# ir-sensor-breakout-mk-1_0.net
KiCad netlist of a schematic drawn in EAGLE
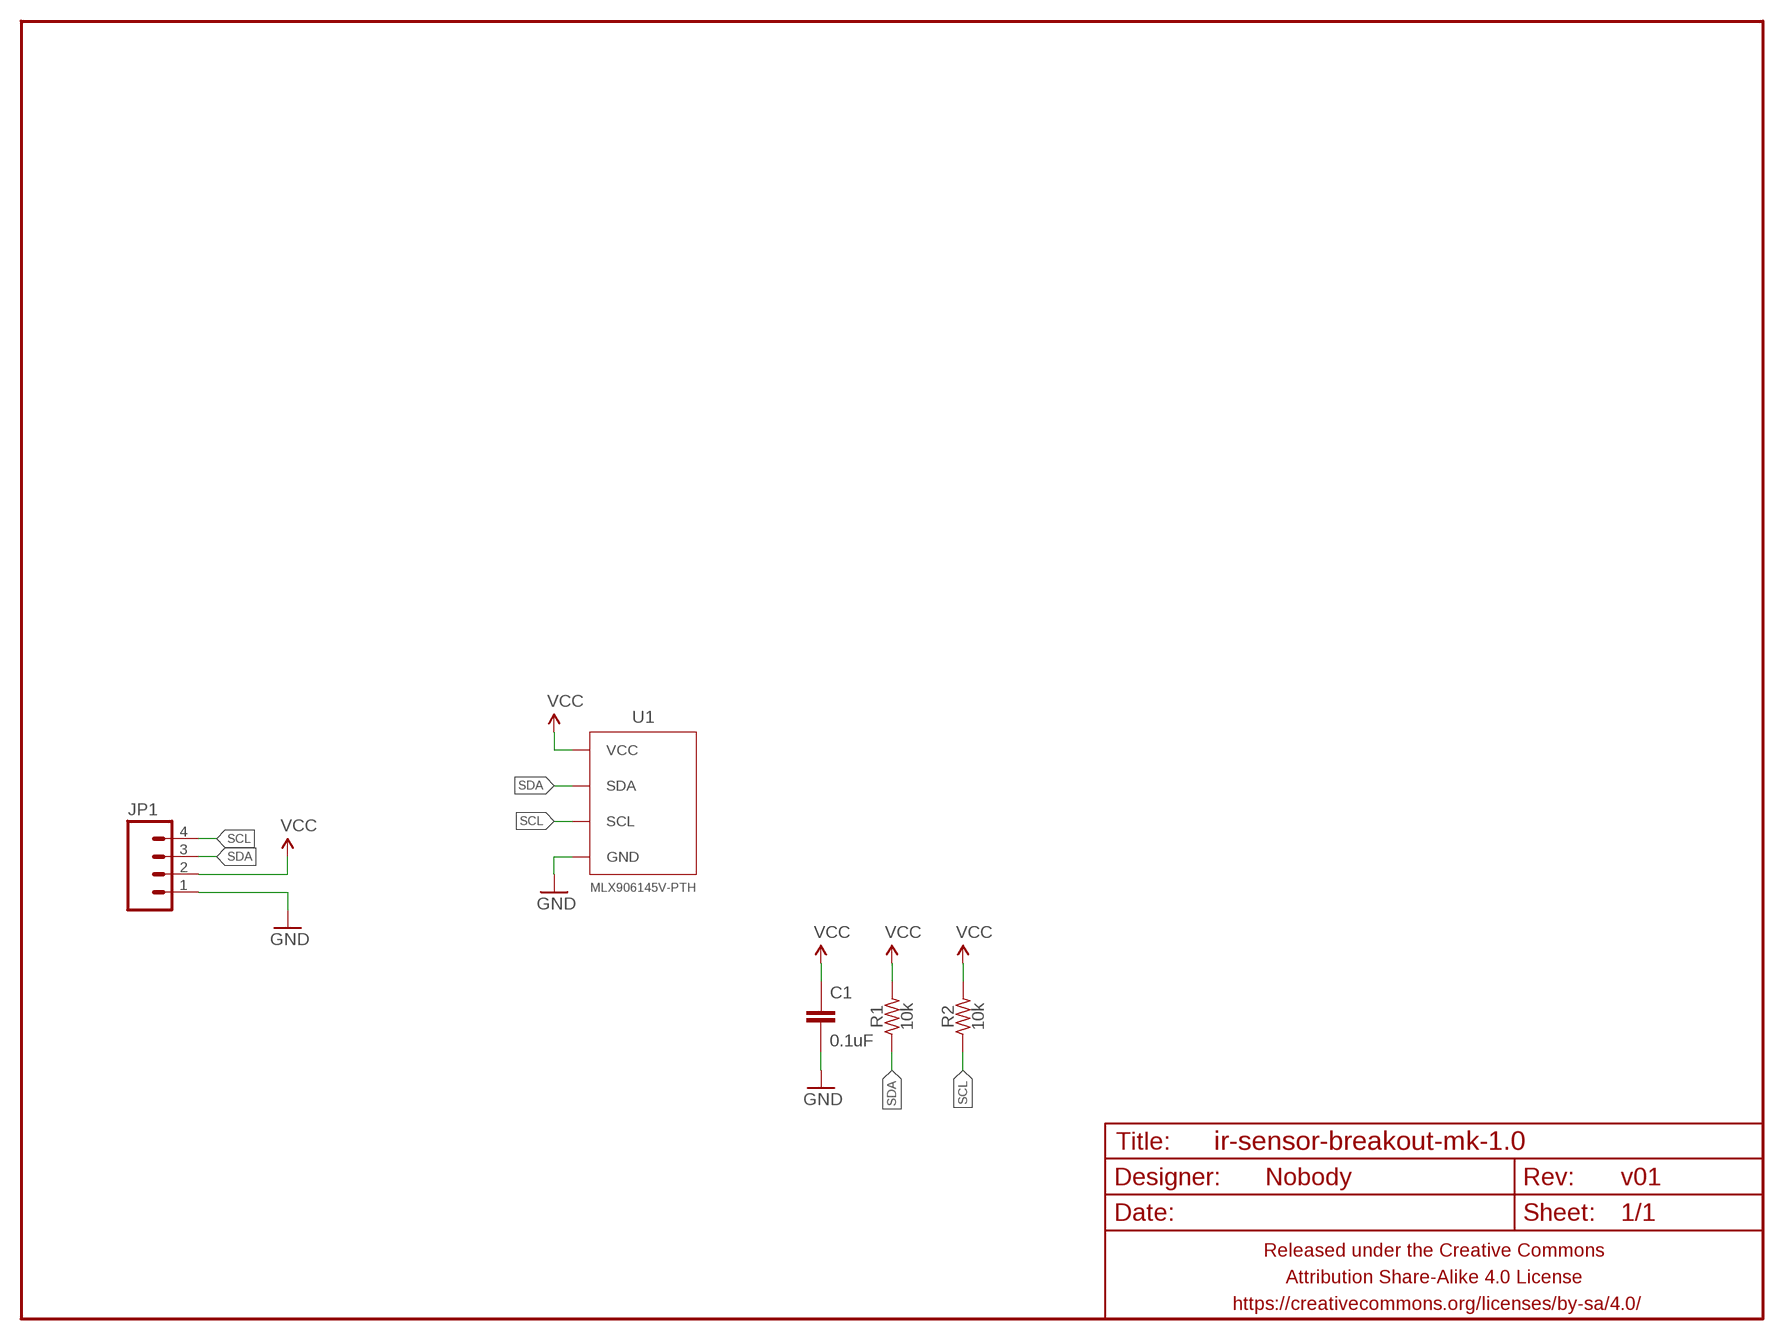
[diagram p0: schematic, sheet 1]

(export (version "E")
  (design (tool "Eeschema 10.0.6"))
  (components
    (comp (ref "C1")
      (value "0.1uF")
      (footprint "eagle-import:C025-024X044")
      (libsource (lib "eagle-import") (part "CAPACITOR-CERAMIC025-024X044"))
    )
    (comp (ref "FRAME1")
      (value "FRAME-LETTERNO_PACKAGE")
      (footprint "eagle-import:DUMMY")
      (fields (field (name "DESIGNER") "Nobody"))
      (libsource (lib "eagle-import") (part "FRAME-LETTERNO_PACKAGE"))
    )
    (comp (ref "JP1")
      (value "M04JST-PTH")
      (footprint "eagle-import:JST-4-PH-RA-PTH")
      (libsource (lib "eagle-import") (part "M04JST-PTH"))
    )
    (comp (ref "R1")
      (value "10k")
      (footprint "eagle-import:RESISTOR-AXIAL-PTH-7.62MM")
      (libsource (lib "eagle-import") (part "RESISTORPTH-AXIAL-7.62MM"))
    )
    (comp (ref "R2")
      (value "10k")
      (footprint "eagle-import:RESISTOR-AXIAL-PTH-7.62MM")
      (libsource (lib "eagle-import") (part "RESISTORPTH-AXIAL-7.62MM"))
    )
    (comp (ref "U1")
      (value "MLX906145V-PTH")
      (footprint "eagle-import:TO-39-4")
      (libsource (lib "eagle-import") (part "MLX906145V-PTH"))
    )
  )
  (nets
    (net (code "1") (name "GND") (class "Default")
      (node (ref "C1") (pin "2") (pinfunction "2_2") (pintype "passive"))
      (node (ref "JP1") (pin "1") (pinfunction "1_1") (pintype "passive"))
      (node (ref "U1") (pin "4") (pinfunction "GND_4") (pintype "bidirectional"))
    )
    (net (code "2") (name "SCL") (class "Default")
      (node (ref "JP1") (pin "4") (pinfunction "4_4") (pintype "passive"))
      (node (ref "R2") (pin "P$1") (pinfunction "1_P$1") (pintype "passive"))
      (node (ref "U1") (pin "1") (pinfunction "SCL_1") (pintype "bidirectional"))
    )
    (net (code "3") (name "SDA") (class "Default")
      (node (ref "JP1") (pin "3") (pinfunction "3_3") (pintype "passive"))
      (node (ref "R1") (pin "P$1") (pinfunction "1_P$1") (pintype "passive"))
      (node (ref "U1") (pin "2") (pinfunction "SDA_2") (pintype "bidirectional"))
    )
    (net (code "4") (name "VCC") (class "Default")
      (node (ref "C1") (pin "1") (pinfunction "1_1") (pintype "passive"))
      (node (ref "JP1") (pin "2") (pinfunction "2_2") (pintype "passive"))
      (node (ref "R1") (pin "P$2") (pinfunction "2_P$2") (pintype "passive"))
      (node (ref "R2") (pin "P$2") (pinfunction "2_P$2") (pintype "passive"))
      (node (ref "U1") (pin "3") (pinfunction "VCC_3") (pintype "bidirectional"))
    )
  )
)
